# OpenPad.net
KiCad netlist of a schematic drawn in EAGLE
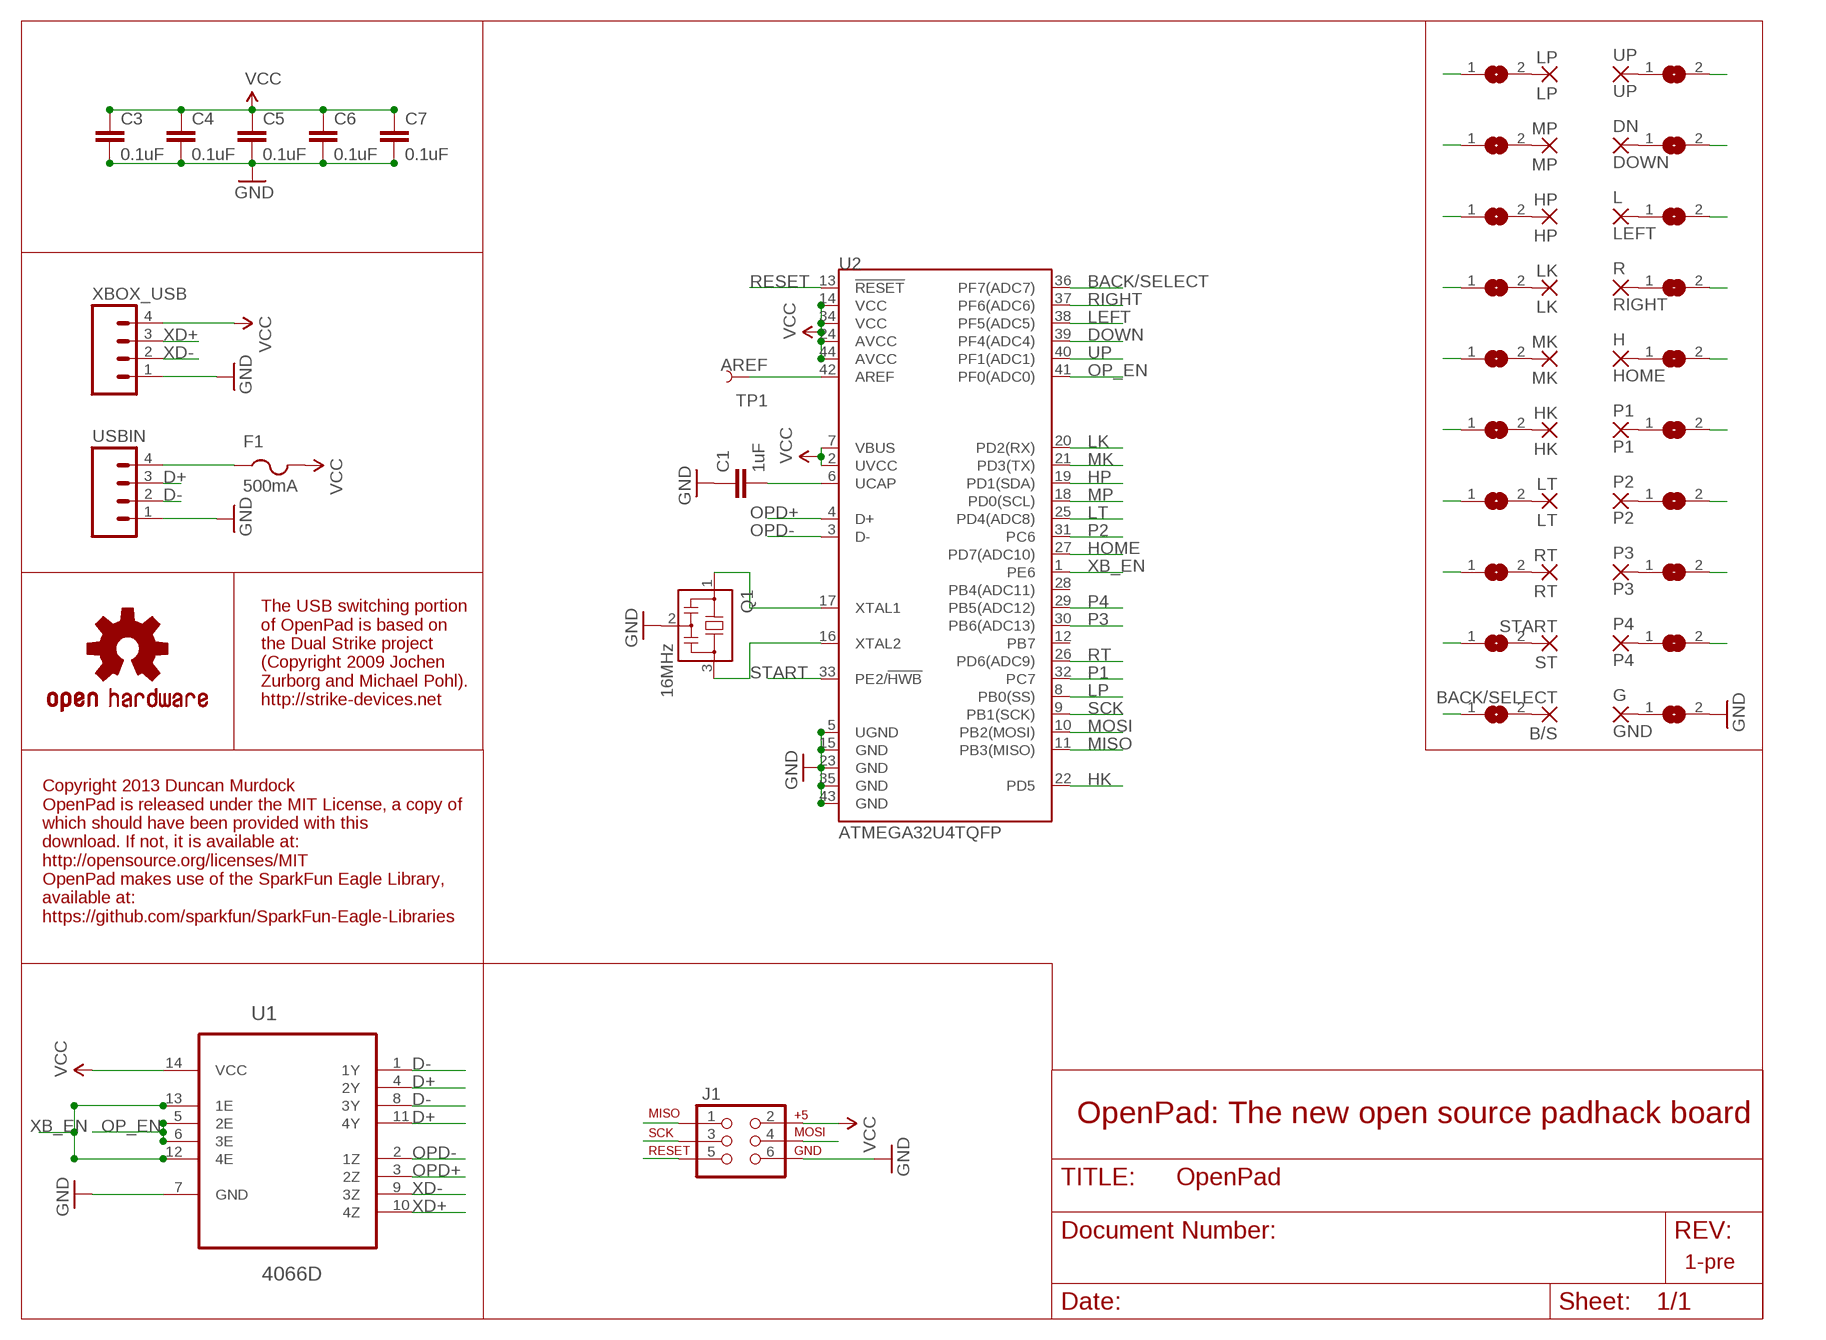
[diagram p0: schematic, sheet 1]

(export (version "E")
  (design (tool "Eeschema 10.0.6"))
  (components
    (comp (ref "B/S")
      (value "BACK/SELECT")
      (footprint "eagle-import:5-2,5")
      (libsource (lib "eagle-import") (part "WIREPADSMD5-2,5"))
    )
    (comp (ref "C1")
      (value "1uF")
      (footprint "eagle-import:0402-CAP")
      (libsource (lib "eagle-import") (part "0.1UF-25V(+80/-20%)(0603)"))
    )
    (comp (ref "C3")
      (value "0.1uF")
      (footprint "eagle-import:0402-CAP")
      (libsource (lib "eagle-import") (part "0.1UF-25V(+80/-20%)(0603)"))
    )
    (comp (ref "C4")
      (value "0.1uF")
      (footprint "eagle-import:0402-CAP")
      (libsource (lib "eagle-import") (part "0.1UF-25V(+80/-20%)(0603)"))
    )
    (comp (ref "C5")
      (value "0.1uF")
      (footprint "eagle-import:0402-CAP")
      (libsource (lib "eagle-import") (part "0.1UF-25V(+80/-20%)(0603)"))
    )
    (comp (ref "C6")
      (value "0.1uF")
      (footprint "eagle-import:0402-CAP")
      (libsource (lib "eagle-import") (part "0.1UF-25V(+80/-20%)(0603)"))
    )
    (comp (ref "C7")
      (value "0.1uF")
      (footprint "eagle-import:0402-CAP")
      (libsource (lib "eagle-import") (part "0.1UF-25V(+80/-20%)(0603)"))
    )
    (comp (ref "DN")
      (value "DOWN")
      (footprint "eagle-import:5-2,5")
      (libsource (lib "eagle-import") (part "WIREPADSMD5-2,5"))
    )
    (comp (ref "F1")
      (value "500mA")
      (footprint "eagle-import:1812")
      (libsource (lib "eagle-import") (part "PTCFUSE-1812"))
    )
    (comp (ref "G")
      (value "GND")
      (footprint "eagle-import:5-2,5")
      (libsource (lib "eagle-import") (part "WIREPADSMD5-2,5"))
    )
    (comp (ref "H")
      (value "HOME")
      (footprint "eagle-import:5-2,5")
      (libsource (lib "eagle-import") (part "WIREPADSMD5-2,5"))
    )
    (comp (ref "HK")
      (value "HK")
      (footprint "eagle-import:5-2,5")
      (libsource (lib "eagle-import") (part "WIREPADSMD5-2,5"))
    )
    (comp (ref "HP")
      (value "HP")
      (footprint "eagle-import:5-2,5")
      (libsource (lib "eagle-import") (part "WIREPADSMD5-2,5"))
    )
    (comp (ref "J1")
      (value "AVR_SPI_PRG_62X3_LOCK")
      (footprint "eagle-import:2X3_LOCK")
      (libsource (lib "eagle-import") (part "AVR_SPI_PRG_62X3_LOCK"))
    )
    (comp (ref "L")
      (value "LEFT")
      (footprint "eagle-import:5-2,5")
      (libsource (lib "eagle-import") (part "WIREPADSMD5-2,5"))
    )
    (comp (ref "LK")
      (value "LK")
      (footprint "eagle-import:5-2,5")
      (libsource (lib "eagle-import") (part "WIREPADSMD5-2,5"))
    )
    (comp (ref "LOGO2")
      (value "OSHW-LOGOM")
      (footprint "eagle-import:OSHW-LOGO-M")
      (libsource (lib "eagle-import") (part "OSHW-LOGOM"))
    )
    (comp (ref "LP")
      (value "LP")
      (footprint "eagle-import:5-2,5")
      (libsource (lib "eagle-import") (part "WIREPADSMD5-2,5"))
    )
    (comp (ref "LT")
      (value "LT")
      (footprint "eagle-import:5-2,5")
      (libsource (lib "eagle-import") (part "WIREPADSMD5-2,5"))
    )
    (comp (ref "MK")
      (value "MK")
      (footprint "eagle-import:5-2,5")
      (libsource (lib "eagle-import") (part "WIREPADSMD5-2,5"))
    )
    (comp (ref "MP")
      (value "MP")
      (footprint "eagle-import:5-2,5")
      (libsource (lib "eagle-import") (part "WIREPADSMD5-2,5"))
    )
    (comp (ref "P1")
      (value "P1")
      (footprint "eagle-import:5-2,5")
      (libsource (lib "eagle-import") (part "WIREPADSMD5-2,5"))
    )
    (comp (ref "P2")
      (value "P2")
      (footprint "eagle-import:5-2,5")
      (libsource (lib "eagle-import") (part "WIREPADSMD5-2,5"))
    )
    (comp (ref "P3")
      (value "P3")
      (footprint "eagle-import:5-2,5")
      (libsource (lib "eagle-import") (part "WIREPADSMD5-2,5"))
    )
    (comp (ref "P4")
      (value "P4")
      (footprint "eagle-import:5-2,5")
      (libsource (lib "eagle-import") (part "WIREPADSMD5-2,5"))
    )
    (comp (ref "Q1")
      (value "16MHz")
      (footprint "eagle-import:CSTCR6M")
      (fields (field (name "MPN") "CSTCR6M00G53-R0"))
      (libsource (lib "eagle-import") (part "CSTCR6M00G53Z"))
    )
    (comp (ref "R")
      (value "RIGHT")
      (footprint "eagle-import:5-2,5")
      (libsource (lib "eagle-import") (part "WIREPADSMD5-2,5"))
    )
    (comp (ref "RT")
      (value "RT")
      (footprint "eagle-import:5-2,5")
      (libsource (lib "eagle-import") (part "WIREPADSMD5-2,5"))
    )
    (comp (ref "SJ1")
      (value "SJW")
      (footprint "eagle-import:SJW")
      (libsource (lib "eagle-import") (part "SJW"))
    )
    (comp (ref "SJ2")
      (value "SJW")
      (footprint "eagle-import:SJW")
      (libsource (lib "eagle-import") (part "SJW"))
    )
    (comp (ref "SJ3")
      (value "SJW")
      (footprint "eagle-import:SJW")
      (libsource (lib "eagle-import") (part "SJW"))
    )
    (comp (ref "SJ4")
      (value "SJW")
      (footprint "eagle-import:SJW")
      (libsource (lib "eagle-import") (part "SJW"))
    )
    (comp (ref "SJ5")
      (value "SJW")
      (footprint "eagle-import:SJW")
      (libsource (lib "eagle-import") (part "SJW"))
    )
    (comp (ref "SJ6")
      (value "SJW")
      (footprint "eagle-import:SJW")
      (libsource (lib "eagle-import") (part "SJW"))
    )
    (comp (ref "SJ7")
      (value "SJW")
      (footprint "eagle-import:SJW")
      (libsource (lib "eagle-import") (part "SJW"))
    )
    (comp (ref "SJ8")
      (value "SJW")
      (footprint "eagle-import:SJW")
      (libsource (lib "eagle-import") (part "SJW"))
    )
    (comp (ref "SJ9")
      (value "SJW")
      (footprint "eagle-import:SJW")
      (libsource (lib "eagle-import") (part "SJW"))
    )
    (comp (ref "SJ10")
      (value "SJW")
      (footprint "eagle-import:SJW")
      (libsource (lib "eagle-import") (part "SJW"))
    )
    (comp (ref "SJ11")
      (value "SJW")
      (footprint "eagle-import:SJW")
      (libsource (lib "eagle-import") (part "SJW"))
    )
    (comp (ref "SJ12")
      (value "SJW")
      (footprint "eagle-import:SJW")
      (libsource (lib "eagle-import") (part "SJW"))
    )
    (comp (ref "SJ13")
      (value "SJW")
      (footprint "eagle-import:SJW")
      (libsource (lib "eagle-import") (part "SJW"))
    )
    (comp (ref "SJ14")
      (value "SJW")
      (footprint "eagle-import:SJW")
      (libsource (lib "eagle-import") (part "SJW"))
    )
    (comp (ref "SJ15")
      (value "SJW")
      (footprint "eagle-import:SJW")
      (libsource (lib "eagle-import") (part "SJW"))
    )
    (comp (ref "SJ16")
      (value "SJW")
      (footprint "eagle-import:SJW")
      (libsource (lib "eagle-import") (part "SJW"))
    )
    (comp (ref "SJ17")
      (value "SJW")
      (footprint "eagle-import:SJW")
      (libsource (lib "eagle-import") (part "SJW"))
    )
    (comp (ref "SJ18")
      (value "SJW")
      (footprint "eagle-import:SJW")
      (libsource (lib "eagle-import") (part "SJW"))
    )
    (comp (ref "SJ19")
      (value "SJW")
      (footprint "eagle-import:SJW")
      (libsource (lib "eagle-import") (part "SJW"))
    )
    (comp (ref "SJ20")
      (value "SJW")
      (footprint "eagle-import:SJW")
      (libsource (lib "eagle-import") (part "SJW"))
    )
    (comp (ref "ST")
      (value "START")
      (footprint "eagle-import:5-2,5")
      (libsource (lib "eagle-import") (part "WIREPADSMD5-2,5"))
    )
    (comp (ref "TP1")
      (value "AREF")
      (footprint "eagle-import:PAD.02X.02")
      (libsource (lib "eagle-import") (part "TEST-POINT2"))
    )
    (comp (ref "U1")
      (value "4066D")
      (footprint "eagle-import:SOIC127P600X175-14N")
      (fields (field (name "MPN") "74HC4066D"))
      (libsource (lib "eagle-import") (part "74HC4066D"))
    )
    (comp (ref "U2")
      (value "ATMEGA32U4TQFP")
      (footprint "eagle-import:SPARKFUN-DIGITALIC_TQFP44")
      (libsource (lib "eagle-import") (part "ATMEGA32U4TQFP"))
    )
    (comp (ref "UP")
      (value "UP")
      (footprint "eagle-import:5-2,5")
      (libsource (lib "eagle-import") (part "WIREPADSMD5-2,5"))
    )
    (comp (ref "USBIN")
      (value "M04LOCK_LONGPADS")
      (footprint "eagle-import:1X04_LOCK_LONGPADS")
      (libsource (lib "eagle-import") (part "M04LOCK_LONGPADS"))
    )
    (comp (ref "XBOX_USB")
      (value "M04LOCK_LONGPADS")
      (footprint "eagle-import:1X04_LOCK_LONGPADS")
      (libsource (lib "eagle-import") (part "M04LOCK_LONGPADS"))
    )
  )
  (nets
    (net (code "1") (name "/BACK{slash}SELECT") (class "Default")
      (node (ref "SJ10") (pin "1") (pinfunction "1_1") (pintype "passive"))
      (node (ref "U2") (pin "36") (pinfunction "PF7(ADC7)_36") (pintype "bidirectional"))
    )
    (net (code "2") (name "/D+") (class "Default")
      (node (ref "U1") (pin "11") (pinfunction "4Y_11") (pintype "bidirectional"))
      (node (ref "U1") (pin "4") (pinfunction "2Y_4") (pintype "bidirectional"))
      (node (ref "USBIN") (pin "3") (pinfunction "3_3") (pintype "passive"))
    )
    (net (code "3") (name "/D-") (class "Default")
      (node (ref "U1") (pin "1") (pinfunction "1Y_1") (pintype "bidirectional"))
      (node (ref "U1") (pin "8") (pinfunction "3Y_8") (pintype "bidirectional"))
      (node (ref "USBIN") (pin "2") (pinfunction "2_2") (pintype "passive"))
    )
    (net (code "4") (name "/DOWN") (class "Default")
      (node (ref "SJ12") (pin "2") (pinfunction "2_2") (pintype "passive"))
      (node (ref "U2") (pin "39") (pinfunction "PF4(ADC4)_39") (pintype "bidirectional"))
    )
    (net (code "5") (name "/HK") (class "Default")
      (node (ref "SJ6") (pin "1") (pinfunction "1_1") (pintype "passive"))
      (node (ref "U2") (pin "22") (pinfunction "PD5_22") (pintype "bidirectional"))
    )
    (net (code "6") (name "/HOME") (class "Default")
      (node (ref "SJ15") (pin "2") (pinfunction "2_2") (pintype "passive"))
      (node (ref "U2") (pin "27") (pinfunction "PD7(ADC10)_27") (pintype "bidirectional"))
    )
    (net (code "7") (name "/HP") (class "Default")
      (node (ref "SJ3") (pin "1") (pinfunction "1_1") (pintype "passive"))
      (node (ref "U2") (pin "19") (pinfunction "PD1(SDA)_19") (pintype "bidirectional"))
    )
    (net (code "8") (name "/LEFT") (class "Default")
      (node (ref "SJ13") (pin "2") (pinfunction "2_2") (pintype "passive"))
      (node (ref "U2") (pin "38") (pinfunction "PF5(ADC5)_38") (pintype "bidirectional"))
    )
    (net (code "9") (name "/LK") (class "Default")
      (node (ref "SJ4") (pin "1") (pinfunction "1_1") (pintype "passive"))
      (node (ref "U2") (pin "20") (pinfunction "PD2(RX)_20") (pintype "bidirectional"))
    )
    (net (code "10") (name "/LP") (class "Default")
      (node (ref "SJ1") (pin "1") (pinfunction "1_1") (pintype "passive"))
      (node (ref "U2") (pin "8") (pinfunction "PB0(SS)_8") (pintype "bidirectional"))
    )
    (net (code "11") (name "/LT") (class "Default")
      (node (ref "SJ7") (pin "1") (pinfunction "1_1") (pintype "passive"))
      (node (ref "U2") (pin "25") (pinfunction "PD4(ADC8)_25") (pintype "bidirectional"))
    )
    (net (code "12") (name "/MISO") (class "Default")
      (node (ref "J1") (pin "1") (pinfunction "1_1") (pintype "passive"))
      (node (ref "U2") (pin "11") (pinfunction "PB3(MISO)_11") (pintype "bidirectional"))
    )
    (net (code "13") (name "/MK") (class "Default")
      (node (ref "SJ5") (pin "1") (pinfunction "1_1") (pintype "passive"))
      (node (ref "U2") (pin "21") (pinfunction "PD3(TX)_21") (pintype "bidirectional"))
    )
    (net (code "14") (name "/MOSI") (class "Default")
      (node (ref "J1") (pin "4") (pinfunction "4_4") (pintype "passive"))
      (node (ref "U2") (pin "10") (pinfunction "PB2(MOSI)_10") (pintype "bidirectional"))
    )
    (net (code "15") (name "/MP") (class "Default")
      (node (ref "SJ2") (pin "1") (pinfunction "1_1") (pintype "passive"))
      (node (ref "U2") (pin "18") (pinfunction "PD0(SCL)_18") (pintype "bidirectional"))
    )
    (net (code "16") (name "/OPD+") (class "Default")
      (node (ref "U1") (pin "3") (pinfunction "2Z_3") (pintype "bidirectional"))
      (node (ref "U2") (pin "4") (pinfunction "D+_4") (pintype "bidirectional"))
    )
    (net (code "17") (name "/OPD-") (class "Default")
      (node (ref "U1") (pin "2") (pinfunction "1Z_2") (pintype "bidirectional"))
      (node (ref "U2") (pin "3") (pinfunction "D-_3") (pintype "bidirectional"))
    )
    (net (code "18") (name "/OP_EN") (class "Default")
      (node (ref "U1") (pin "5") (pinfunction "2E_5") (pintype "input"))
      (node (ref "U1") (pin "6") (pinfunction "3E_6") (pintype "input"))
      (node (ref "U2") (pin "41") (pinfunction "PF0(ADC0)_41") (pintype "bidirectional"))
    )
    (net (code "19") (name "/P1") (class "Default")
      (node (ref "SJ16") (pin "2") (pinfunction "2_2") (pintype "passive"))
      (node (ref "U2") (pin "32") (pinfunction "PC7_32") (pintype "bidirectional"))
    )
    (net (code "20") (name "/P2") (class "Default")
      (node (ref "SJ17") (pin "2") (pinfunction "2_2") (pintype "passive"))
      (node (ref "U2") (pin "31") (pinfunction "PC6_31") (pintype "bidirectional"))
    )
    (net (code "21") (name "/P3") (class "Default")
      (node (ref "SJ18") (pin "2") (pinfunction "2_2") (pintype "passive"))
      (node (ref "U2") (pin "30") (pinfunction "PB6(ADC13)_30") (pintype "bidirectional"))
    )
    (net (code "22") (name "/P4") (class "Default")
      (node (ref "SJ19") (pin "2") (pinfunction "2_2") (pintype "passive"))
      (node (ref "U2") (pin "29") (pinfunction "PB5(ADC12)_29") (pintype "bidirectional"))
    )
    (net (code "23") (name "/RESET") (class "Default")
      (node (ref "J1") (pin "5") (pinfunction "5_5") (pintype "passive"))
      (node (ref "U2") (pin "13") (pinfunction "~{RESET}_13") (pintype "bidirectional"))
    )
    (net (code "24") (name "/RIGHT") (class "Default")
      (node (ref "SJ14") (pin "2") (pinfunction "2_2") (pintype "passive"))
      (node (ref "U2") (pin "37") (pinfunction "PF6(ADC6)_37") (pintype "bidirectional"))
    )
    (net (code "25") (name "/RT") (class "Default")
      (node (ref "SJ8") (pin "1") (pinfunction "1_1") (pintype "passive"))
      (node (ref "U2") (pin "26") (pinfunction "PD6(ADC9)_26") (pintype "bidirectional"))
    )
    (net (code "26") (name "/SCK") (class "Default")
      (node (ref "J1") (pin "3") (pinfunction "3_3") (pintype "passive"))
      (node (ref "U2") (pin "9") (pinfunction "PB1(SCK)_9") (pintype "bidirectional"))
    )
    (net (code "27") (name "/START") (class "Default")
      (node (ref "SJ9") (pin "1") (pinfunction "1_1") (pintype "passive"))
      (node (ref "U2") (pin "33") (pinfunction "PE2/~{HWB}_33") (pintype "bidirectional"))
    )
    (net (code "28") (name "/UP") (class "Default")
      (node (ref "SJ11") (pin "2") (pinfunction "2_2") (pintype "passive"))
      (node (ref "U2") (pin "40") (pinfunction "PF1(ADC1)_40") (pintype "bidirectional"))
    )
    (net (code "29") (name "/XB_EN") (class "Default")
      (node (ref "U1") (pin "12") (pinfunction "4E_12") (pintype "input"))
      (node (ref "U1") (pin "13") (pinfunction "1E_13") (pintype "input"))
      (node (ref "U2") (pin "1") (pinfunction "PE6_1") (pintype "bidirectional"))
    )
    (net (code "30") (name "/XD+") (class "Default")
      (node (ref "U1") (pin "10") (pinfunction "4Z_10") (pintype "bidirectional"))
      (node (ref "XBOX_USB") (pin "3") (pinfunction "3_3") (pintype "passive"))
    )
    (net (code "31") (name "/XD-") (class "Default")
      (node (ref "U1") (pin "9") (pinfunction "3Z_9") (pintype "bidirectional"))
      (node (ref "XBOX_USB") (pin "2") (pinfunction "2_2") (pintype "passive"))
    )
    (net (code "32") (name "GND") (class "Default")
      (node (ref "C1") (pin "1") (pinfunction "1_1") (pintype "passive"))
      (node (ref "C3") (pin "2") (pinfunction "2_2") (pintype "passive"))
      (node (ref "C4") (pin "2") (pinfunction "2_2") (pintype "passive"))
      (node (ref "C5") (pin "2") (pinfunction "2_2") (pintype "passive"))
      (node (ref "C6") (pin "2") (pinfunction "2_2") (pintype "passive"))
      (node (ref "C7") (pin "2") (pinfunction "2_2") (pintype "passive"))
      (node (ref "J1") (pin "6") (pinfunction "6_6") (pintype "passive"))
      (node (ref "Q1") (pin "2") (pinfunction "2_2") (pintype "passive"))
      (node (ref "SJ20") (pin "2") (pinfunction "2_2") (pintype "passive"))
      (node (ref "U1") (pin "7") (pinfunction "GND_7") (pintype "passive"))
      (node (ref "U2") (pin "15") (pinfunction "GND_15") (pintype "bidirectional"))
      (node (ref "U2") (pin "23") (pinfunction "GND_23") (pintype "bidirectional"))
      (node (ref "U2") (pin "35") (pinfunction "GND_35") (pintype "bidirectional"))
      (node (ref "U2") (pin "43") (pinfunction "GND_43") (pintype "bidirectional"))
      (node (ref "U2") (pin "5") (pinfunction "UGND_5") (pintype "bidirectional"))
      (node (ref "USBIN") (pin "1") (pinfunction "1_1") (pintype "passive"))
      (node (ref "XBOX_USB") (pin "1") (pinfunction "1_1") (pintype "passive"))
    )
    (net (code "33") (name "Net-(B/S-P)") (class "Default")
      (node (ref "B/S") (pin "1") (pinfunction "P_1") (pintype "passive"))
      (node (ref "SJ10") (pin "2") (pinfunction "2_2") (pintype "passive"))
    )
    (net (code "34") (name "Net-(DN-P)") (class "Default")
      (node (ref "DN") (pin "1") (pinfunction "P_1") (pintype "passive"))
      (node (ref "SJ12") (pin "1") (pinfunction "1_1") (pintype "passive"))
    )
    (net (code "35") (name "Net-(F1-Pad1)") (class "Default")
      (node (ref "F1") (pin "1") (pinfunction "1_1") (pintype "passive"))
      (node (ref "USBIN") (pin "4") (pinfunction "4_4") (pintype "passive"))
    )
    (net (code "36") (name "Net-(G-P)") (class "Default")
      (node (ref "G") (pin "1") (pinfunction "P_1") (pintype "passive"))
      (node (ref "SJ20") (pin "1") (pinfunction "1_1") (pintype "passive"))
    )
    (net (code "37") (name "Net-(H-P)") (class "Default")
      (node (ref "H") (pin "1") (pinfunction "P_1") (pintype "passive"))
      (node (ref "SJ15") (pin "1") (pinfunction "1_1") (pintype "passive"))
    )
    (net (code "38") (name "Net-(HK-P)") (class "Default")
      (node (ref "HK") (pin "1") (pinfunction "P_1") (pintype "passive"))
      (node (ref "SJ6") (pin "2") (pinfunction "2_2") (pintype "passive"))
    )
    (net (code "39") (name "Net-(HP-P)") (class "Default")
      (node (ref "HP") (pin "1") (pinfunction "P_1") (pintype "passive"))
      (node (ref "SJ3") (pin "2") (pinfunction "2_2") (pintype "passive"))
    )
    (net (code "40") (name "Net-(L-P)") (class "Default")
      (node (ref "L") (pin "1") (pinfunction "P_1") (pintype "passive"))
      (node (ref "SJ13") (pin "1") (pinfunction "1_1") (pintype "passive"))
    )
    (net (code "41") (name "Net-(LK-P)") (class "Default")
      (node (ref "LK") (pin "1") (pinfunction "P_1") (pintype "passive"))
      (node (ref "SJ4") (pin "2") (pinfunction "2_2") (pintype "passive"))
    )
    (net (code "42") (name "Net-(LP-P)") (class "Default")
      (node (ref "LP") (pin "1") (pinfunction "P_1") (pintype "passive"))
      (node (ref "SJ1") (pin "2") (pinfunction "2_2") (pintype "passive"))
    )
    (net (code "43") (name "Net-(LT-P)") (class "Default")
      (node (ref "LT") (pin "1") (pinfunction "P_1") (pintype "passive"))
      (node (ref "SJ7") (pin "2") (pinfunction "2_2") (pintype "passive"))
    )
    (net (code "44") (name "Net-(MK-P)") (class "Default")
      (node (ref "MK") (pin "1") (pinfunction "P_1") (pintype "passive"))
      (node (ref "SJ5") (pin "2") (pinfunction "2_2") (pintype "passive"))
    )
    (net (code "45") (name "Net-(MP-P)") (class "Default")
      (node (ref "MP") (pin "1") (pinfunction "P_1") (pintype "passive"))
      (node (ref "SJ2") (pin "2") (pinfunction "2_2") (pintype "passive"))
    )
    (net (code "46") (name "Net-(P1-P)") (class "Default")
      (node (ref "P1") (pin "1") (pinfunction "P_1") (pintype "passive"))
      (node (ref "SJ16") (pin "1") (pinfunction "1_1") (pintype "passive"))
    )
    (net (code "47") (name "Net-(P2-P)") (class "Default")
      (node (ref "P2") (pin "1") (pinfunction "P_1") (pintype "passive"))
      (node (ref "SJ17") (pin "1") (pinfunction "1_1") (pintype "passive"))
    )
    (net (code "48") (name "Net-(P3-P)") (class "Default")
      (node (ref "P3") (pin "1") (pinfunction "P_1") (pintype "passive"))
      (node (ref "SJ18") (pin "1") (pinfunction "1_1") (pintype "passive"))
    )
    (net (code "49") (name "Net-(P4-P)") (class "Default")
      (node (ref "P4") (pin "1") (pinfunction "P_1") (pintype "passive"))
      (node (ref "SJ19") (pin "1") (pinfunction "1_1") (pintype "passive"))
    )
    (net (code "50") (name "Net-(R-P)") (class "Default")
      (node (ref "R") (pin "1") (pinfunction "P_1") (pintype "passive"))
      (node (ref "SJ14") (pin "1") (pinfunction "1_1") (pintype "passive"))
    )
    (net (code "51") (name "Net-(RT-P)") (class "Default")
      (node (ref "RT") (pin "1") (pinfunction "P_1") (pintype "passive"))
      (node (ref "SJ8") (pin "2") (pinfunction "2_2") (pintype "passive"))
    )
    (net (code "52") (name "Net-(ST-P)") (class "Default")
      (node (ref "SJ9") (pin "2") (pinfunction "2_2") (pintype "passive"))
      (node (ref "ST") (pin "1") (pinfunction "P_1") (pintype "passive"))
    )
    (net (code "53") (name "Net-(TP1-1)") (class "Default")
      (node (ref "TP1") (pin "P$1") (pinfunction "1_P$1") (pintype "bidirectional"))
      (node (ref "U2") (pin "42") (pinfunction "AREF_42") (pintype "bidirectional"))
    )
    (net (code "54") (name "Net-(U2-UCAP)") (class "Default")
      (node (ref "C1") (pin "2") (pinfunction "2_2") (pintype "passive"))
      (node (ref "U2") (pin "6") (pinfunction "UCAP_6") (pintype "bidirectional"))
    )
    (net (code "55") (name "Net-(U2-XTAL1)") (class "Default")
      (node (ref "Q1") (pin "1") (pinfunction "1_1") (pintype "passive"))
      (node (ref "U2") (pin "17") (pinfunction "XTAL1_17") (pintype "bidirectional"))
    )
    (net (code "56") (name "Net-(U2-XTAL2)") (class "Default")
      (node (ref "Q1") (pin "3") (pinfunction "3_3") (pintype "passive"))
      (node (ref "U2") (pin "16") (pinfunction "XTAL2_16") (pintype "bidirectional"))
    )
    (net (code "57") (name "Net-(UP-P)") (class "Default")
      (node (ref "SJ11") (pin "1") (pinfunction "1_1") (pintype "passive"))
      (node (ref "UP") (pin "1") (pinfunction "P_1") (pintype "passive"))
    )
    (net (code "58") (name "VCC") (class "Default")
      (node (ref "C3") (pin "1") (pinfunction "1_1") (pintype "passive"))
      (node (ref "C4") (pin "1") (pinfunction "1_1") (pintype "passive"))
      (node (ref "C5") (pin "1") (pinfunction "1_1") (pintype "passive"))
      (node (ref "C6") (pin "1") (pinfunction "1_1") (pintype "passive"))
      (node (ref "C7") (pin "1") (pinfunction "1_1") (pintype "passive"))
      (node (ref "F1") (pin "2") (pinfunction "2_2") (pintype "passive"))
      (node (ref "J1") (pin "2") (pinfunction "2_2") (pintype "passive"))
      (node (ref "U1") (pin "14") (pinfunction "VCC_14") (pintype "power_in"))
      (node (ref "U2") (pin "14") (pinfunction "VCC_14") (pintype "bidirectional"))
      (node (ref "U2") (pin "2") (pinfunction "UVCC_2") (pintype "bidirectional"))
      (node (ref "U2") (pin "24") (pinfunction "AVCC_24") (pintype "bidirectional"))
      (node (ref "U2") (pin "34") (pinfunction "VCC_34") (pintype "bidirectional"))
      (node (ref "U2") (pin "44") (pinfunction "AVCC_44") (pintype "bidirectional"))
      (node (ref "U2") (pin "7") (pinfunction "VBUS_7") (pintype "bidirectional"))
      (node (ref "XBOX_USB") (pin "4") (pinfunction "4_4") (pintype "passive"))
    )
    (net (code "59") (name "unconnected-(U2-PB4(ADC11)-Pad28)") (class "Default")
      (node (ref "U2") (pin "28") (pinfunction "PB4(ADC11)_28") (pintype "bidirectional"))
    )
    (net (code "60") (name "unconnected-(U2-PB7-Pad12)") (class "Default")
      (node (ref "U2") (pin "12") (pinfunction "PB7_12") (pintype "bidirectional"))
    )
  )
)
